# balloon_system.net
KiCad netlist of a schematic drawn in Altium Designer
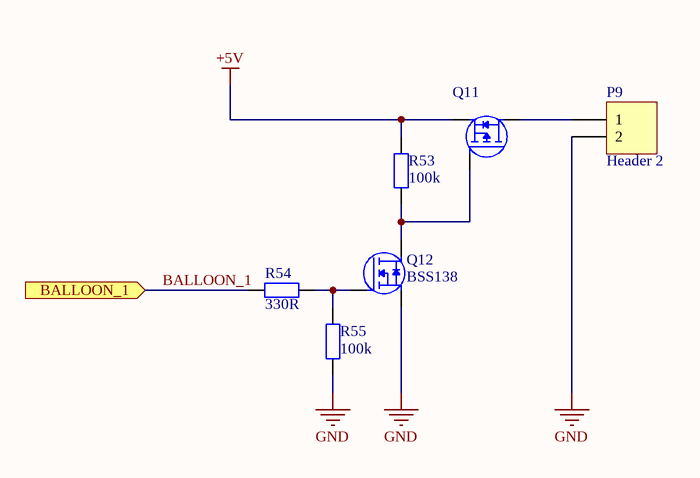
[diagram p0: balloon_system.SchDoc]

(export (version "E")
  (design (tool "Eeschema 10.0.6"))
  (components
    (comp (ref "P9")
      (value "Header 2")
      (footprint "HDR1X2")
      (description "Header, 2-Pin")
      (fields (field (name "PUBLISHER") "Altium Limited"))
      (libsource (lib "Miscellaneous Connectors") (part "Header 2"))
    )
    (comp (ref "Q11")
      (value "SISH625DN-T1-GE3")
      (footprint "SISH625DN")
      (description "P-Channel 30V 17.3A (Ta), 35A (Tc) 3.7W (Ta), 52W (Tc) Surface Mount PowerPAK® 1212-8SH")
      (fields (field (name "MANUFACTURER") "Vishay Siliconix"))
      (libsource (lib "alfasat_lib_eps") (part "SISH625DN-T1"))
    )
    (comp (ref "Q12")
      (value "BSS138")
      (footprint "SOT23")
      (description "N-Channel Logic Level Enhancement Mode Field Effect Transistor")
      (fields (field (name "MANUFACTURER") "Diodes Incorporated"))
      (libsource (lib "alfasat_parts_lib") (part "BSS138"))
    )
    (comp (ref "R53")
      (value "100k")
      (footprint "R0603_IPC_MD")
      (description "RES 100K OHM 1% 1/10W 0603")
      (fields
        (field (name "MANUFACTURER") "Bourns Inc.")
        (field (name "MANUFACTURER PART NUMBER") "RMCF0603FT100K")
      )
      (libsource (lib "alfasat_parts_lib") (part "RMCF0603FT100K"))
    )
    (comp (ref "R54")
      (value "330R")
      (footprint "R0603_IPC_MD")
      (description "RES SMD 330 OHM 5% 1/10W 0603")
      (fields
        (field (name "MANUFACTURER") "Bourns Inc.")
        (field (name "MANUFACTURER PART NUMBER") "CR0603-JW-331ELF")
      )
      (libsource (lib "alfasat_parts_lib") (part "CR0603-JW-331ELF"))
    )
    (comp (ref "R55")
      (value "100k")
      (footprint "R0603_IPC_MD")
      (description "RES 100K OHM 1% 1/10W 0603")
      (fields
        (field (name "MANUFACTURER") "Bourns Inc.")
        (field (name "MANUFACTURER PART NUMBER") "RMCF0603FT100K")
      )
      (libsource (lib "alfasat_parts_lib") (part "RMCF0603FT100K"))
    )
  )
  (nets
    (net (code "1") (name "+5V") (class "Default")
      (node (ref "Q11") (pin "1") (pinfunction "S_1") (pintype "passive"))
      (node (ref "R53") (pin "1") (pinfunction "1_1") (pintype "passive"))
    )
    (net (code "2") (name "/BALLOON_1") (class "Default")
      (node (ref "R54") (pin "2") (pinfunction "2_2") (pintype "passive"))
    )
    (net (code "3") (name "GND") (class "Default")
      (node (ref "P9") (pin "2") (pinfunction "2_2") (pintype "passive"))
      (node (ref "Q12") (pin "2") (pinfunction "S_2") (pintype "passive"))
      (node (ref "R55") (pin "2") (pinfunction "2_2") (pintype "passive"))
    )
    (net (code "4") (name "Net-(Q11-D)") (class "Default")
      (node (ref "P9") (pin "1") (pinfunction "1_1") (pintype "passive"))
      (node (ref "Q11") (pin "3") (pinfunction "D_3") (pintype "passive"))
    )
    (net (code "5") (name "Net-(Q11-G)") (class "Default")
      (node (ref "Q11") (pin "2") (pinfunction "G_2") (pintype "passive"))
      (node (ref "Q12") (pin "3") (pinfunction "D_3") (pintype "passive"))
      (node (ref "R53") (pin "2") (pinfunction "2_2") (pintype "passive"))
    )
    (net (code "6") (name "Net-(Q12-G)") (class "Default")
      (node (ref "Q12") (pin "1") (pinfunction "G_1") (pintype "passive"))
      (node (ref "R54") (pin "1") (pinfunction "1_1") (pintype "passive"))
      (node (ref "R55") (pin "1") (pinfunction "1_1") (pintype "passive"))
    )
  )
)
